# OSSC_HDMI_Audio.net
KiCad netlist of a schematic drawn in EAGLE
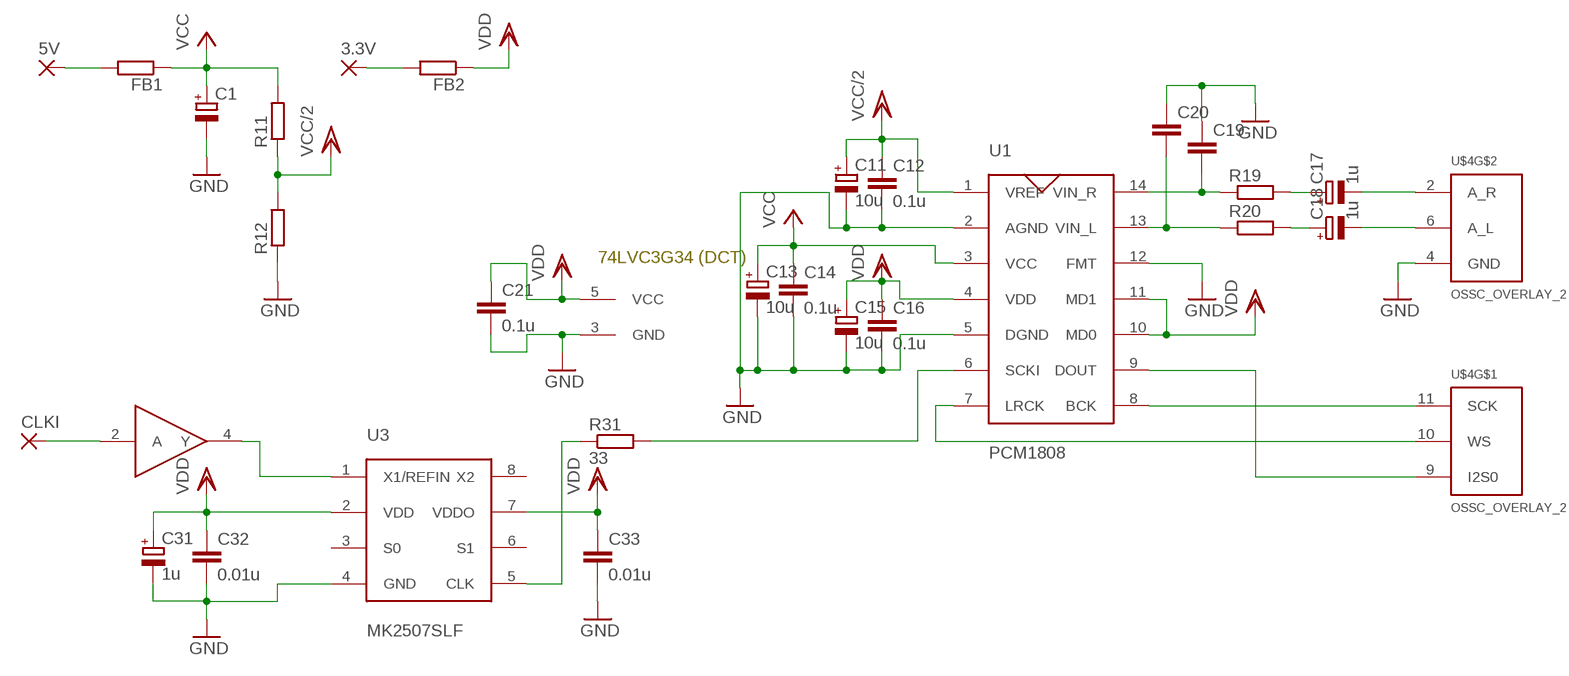
[diagram p0: schematic, sheet 1]

(export (version "E")
  (design (tool "Eeschema 10.0.6"))
  (components
    (comp (ref "3.3V")
      (value "SMD2")
      (footprint "eagle-import:SMD1,27-2,54")
      (libsource (lib "eagle-import") (part "SMD2"))
    )
    (comp (ref "5V")
      (value "SMD2")
      (footprint "eagle-import:SMD1,27-2,54")
      (libsource (lib "eagle-import") (part "SMD2"))
    )
    (comp (ref "C1")
      (value "CPOL-EUSMCC")
      (footprint "eagle-import:SMC_C")
      (libsource (lib "eagle-import") (part "CPOL-EUSMCC"))
    )
    (comp (ref "C11")
      (value "10u")
      (footprint "eagle-import:SMC_A")
      (libsource (lib "eagle-import") (part "CPOL-EUSMCA"))
    )
    (comp (ref "C12")
      (value "0.1u")
      (footprint "eagle-import:C0603")
      (libsource (lib "eagle-import") (part "C-EUC0603"))
    )
    (comp (ref "C13")
      (value "10u")
      (footprint "eagle-import:SMC_A")
      (libsource (lib "eagle-import") (part "CPOL-EUSMCA"))
    )
    (comp (ref "C14")
      (value "0.1u")
      (footprint "eagle-import:C0603")
      (libsource (lib "eagle-import") (part "C-EUC0603"))
    )
    (comp (ref "C15")
      (value "10u")
      (footprint "eagle-import:SMC_A")
      (libsource (lib "eagle-import") (part "CPOL-EUSMCA"))
    )
    (comp (ref "C16")
      (value "0.1u")
      (footprint "eagle-import:C0603")
      (libsource (lib "eagle-import") (part "C-EUC0603"))
    )
    (comp (ref "C17")
      (value "1u")
      (footprint "eagle-import:SMC_A")
      (libsource (lib "eagle-import") (part "CPOL-EUSMCA"))
    )
    (comp (ref "C18")
      (value "1u")
      (footprint "eagle-import:SMC_A")
      (libsource (lib "eagle-import") (part "CPOL-EUSMCA"))
    )
    (comp (ref "C19")
      (value "C-EUC0603")
      (footprint "eagle-import:C0603")
      (libsource (lib "eagle-import") (part "C-EUC0603"))
    )
    (comp (ref "C20")
      (value "C-EUC0603")
      (footprint "eagle-import:C0603")
      (libsource (lib "eagle-import") (part "C-EUC0603"))
    )
    (comp (ref "C21")
      (value "0.1u")
      (footprint "eagle-import:C0603")
      (libsource (lib "eagle-import") (part "C-EUC0603"))
    )
    (comp (ref "C31")
      (value "1u")
      (footprint "eagle-import:SMC_A")
      (libsource (lib "eagle-import") (part "CPOL-EUSMCA"))
    )
    (comp (ref "C32")
      (value "0.01u")
      (footprint "eagle-import:C0603")
      (libsource (lib "eagle-import") (part "C-EUC0603"))
    )
    (comp (ref "C33")
      (value "0.01u")
      (footprint "eagle-import:C0603")
      (libsource (lib "eagle-import") (part "C-EUC0603"))
    )
    (comp (ref "CLKI")
      (value "SMD2")
      (footprint "eagle-import:SMD1,27-2,54")
      (libsource (lib "eagle-import") (part "SMD2"))
    )
    (comp (ref "FB1")
      (value "R-EU_R0603")
      (footprint "eagle-import:R0603")
      (libsource (lib "eagle-import") (part "R-EU_R0603"))
    )
    (comp (ref "FB2")
      (value "R-EU_R0603")
      (footprint "eagle-import:R0603")
      (libsource (lib "eagle-import") (part "R-EU_R0603"))
    )
    (comp (ref "R11")
      (value "R-EU_R0603")
      (footprint "eagle-import:R0603")
      (libsource (lib "eagle-import") (part "R-EU_R0603"))
    )
    (comp (ref "R12")
      (value "R-EU_R0603")
      (footprint "eagle-import:R0603")
      (libsource (lib "eagle-import") (part "R-EU_R0603"))
    )
    (comp (ref "R19")
      (value "R-EU_R0603")
      (footprint "eagle-import:R0603")
      (libsource (lib "eagle-import") (part "R-EU_R0603"))
    )
    (comp (ref "R20")
      (value "R-EU_R0603")
      (footprint "eagle-import:R0603")
      (libsource (lib "eagle-import") (part "R-EU_R0603"))
    )
    (comp (ref "R31")
      (value "33")
      (footprint "eagle-import:R0603")
      (libsource (lib "eagle-import") (part "R-EU_R0603"))
    )
    (comp (ref "U$4")
      (value "OSSC_OVERLAY_2")
      (footprint "eagle-import:OSSC_OVERLAY_2")
      (libsource (lib "eagle-import") (part "OSSC_OVERLAY_2"))
    )
    (comp (ref "U1")
      (value "PCM1808")
      (footprint "eagle-import:PCM1808")
      (libsource (lib "eagle-import") (part "PCM1808"))
    )
    (comp (ref "U2")
      (value "74LVC1G34")
      (footprint "eagle-import:74LVC1G34DCK")
      (libsource (lib "eagle-import") (part "74LVC1G34"))
    )
    (comp (ref "U3")
      (value "MK2507SLF")
      (footprint "eagle-import:SOIC8")
      (libsource (lib "eagle-import") (part "MK2507SLF"))
    )
  )
  (nets
    (net (code "1") (name "GND") (class "Default")
      (node (ref "C1") (pin "-") (pinfunction "-_-") (pintype "passive"))
      (node (ref "C11") (pin "-") (pinfunction "-_-") (pintype "passive"))
      (node (ref "C12") (pin "2") (pinfunction "2_2") (pintype "passive"))
      (node (ref "C13") (pin "-") (pinfunction "-_-") (pintype "passive"))
      (node (ref "C14") (pin "2") (pinfunction "2_2") (pintype "passive"))
      (node (ref "C15") (pin "-") (pinfunction "-_-") (pintype "passive"))
      (node (ref "C16") (pin "2") (pinfunction "2_2") (pintype "passive"))
      (node (ref "C19") (pin "1") (pinfunction "1_1") (pintype "passive"))
      (node (ref "C20") (pin "1") (pinfunction "1_1") (pintype "passive"))
      (node (ref "C21") (pin "2") (pinfunction "2_2") (pintype "passive"))
      (node (ref "C31") (pin "-") (pinfunction "-_-") (pintype "passive"))
      (node (ref "C32") (pin "2") (pinfunction "2_2") (pintype "passive"))
      (node (ref "C33") (pin "2") (pinfunction "2_2") (pintype "passive"))
      (node (ref "R12") (pin "1") (pinfunction "1_1") (pintype "passive"))
      (node (ref "U$4") (pin "4") (pinfunction "GND_4") (pintype "bidirectional"))
      (node (ref "U1") (pin "12") (pinfunction "FMT_12") (pintype "bidirectional"))
      (node (ref "U1") (pin "2") (pinfunction "AGND_2") (pintype "bidirectional"))
      (node (ref "U1") (pin "5") (pinfunction "DGND_5") (pintype "bidirectional"))
      (node (ref "U2") (pin "3") (pinfunction "GND_3") (pintype "bidirectional"))
      (node (ref "U3") (pin "4") (pinfunction "GND_4") (pintype "bidirectional"))
    )
    (net (code "2") (name "Net-(3.3V-P)") (class "Default")
      (node (ref "3.3V") (pin "1") (pinfunction "P_1") (pintype "passive"))
      (node (ref "FB2") (pin "2") (pinfunction "2_2") (pintype "passive"))
    )
    (net (code "3") (name "Net-(5V-P)") (class "Default")
      (node (ref "5V") (pin "1") (pinfunction "P_1") (pintype "passive"))
      (node (ref "FB1") (pin "2") (pinfunction "2_2") (pintype "passive"))
    )
    (net (code "4") (name "Net-(C17-Pad+)") (class "Default")
      (node (ref "C17") (pin "+") (pinfunction "+_+") (pintype "passive"))
      (node (ref "R19") (pin "2") (pinfunction "2_2") (pintype "passive"))
    )
    (net (code "5") (name "Net-(C18-Pad+)") (class "Default")
      (node (ref "C18") (pin "+") (pinfunction "+_+") (pintype "passive"))
      (node (ref "R20") (pin "2") (pinfunction "2_2") (pintype "passive"))
    )
    (net (code "6") (name "Net-(CLKI-P)") (class "Default")
      (node (ref "CLKI") (pin "1") (pinfunction "P_1") (pintype "passive"))
      (node (ref "U2") (pin "2") (pinfunction "A_2") (pintype "bidirectional"))
    )
    (net (code "7") (name "Net-(U$4A-I2S0)") (class "Default")
      (node (ref "U$4") (pin "9") (pinfunction "I2S0_9") (pintype "bidirectional"))
      (node (ref "U1") (pin "9") (pinfunction "DOUT_9") (pintype "bidirectional"))
    )
    (net (code "8") (name "Net-(U$4A-SCK)") (class "Default")
      (node (ref "U$4") (pin "11") (pinfunction "SCK_11") (pintype "bidirectional"))
      (node (ref "U1") (pin "8") (pinfunction "BCK_8") (pintype "bidirectional"))
    )
    (net (code "9") (name "Net-(U$4A-WS)") (class "Default")
      (node (ref "U$4") (pin "10") (pinfunction "WS_10") (pintype "bidirectional"))
      (node (ref "U1") (pin "7") (pinfunction "LRCK_7") (pintype "bidirectional"))
    )
    (net (code "10") (name "Net-(U$4B-A_L)") (class "Default")
      (node (ref "C18") (pin "-") (pinfunction "-_-") (pintype "passive"))
      (node (ref "U$4") (pin "6") (pinfunction "A_L_6") (pintype "bidirectional"))
    )
    (net (code "11") (name "Net-(U$4B-A_R)") (class "Default")
      (node (ref "C17") (pin "-") (pinfunction "-_-") (pintype "passive"))
      (node (ref "U$4") (pin "2") (pinfunction "A_R_2") (pintype "bidirectional"))
    )
    (net (code "12") (name "Net-(U1-SCKI)") (class "Default")
      (node (ref "R31") (pin "2") (pinfunction "2_2") (pintype "passive"))
      (node (ref "U1") (pin "6") (pinfunction "SCKI_6") (pintype "bidirectional"))
    )
    (net (code "13") (name "Net-(U1-VIN_L)") (class "Default")
      (node (ref "C20") (pin "2") (pinfunction "2_2") (pintype "passive"))
      (node (ref "R20") (pin "1") (pinfunction "1_1") (pintype "passive"))
      (node (ref "U1") (pin "13") (pinfunction "VIN_L_13") (pintype "bidirectional"))
    )
    (net (code "14") (name "Net-(U1-VIN_R)") (class "Default")
      (node (ref "C19") (pin "2") (pinfunction "2_2") (pintype "passive"))
      (node (ref "R19") (pin "1") (pinfunction "1_1") (pintype "passive"))
      (node (ref "U1") (pin "14") (pinfunction "VIN_R_14") (pintype "bidirectional"))
    )
    (net (code "15") (name "Net-(U2A-Y)") (class "Default")
      (node (ref "U2") (pin "4") (pinfunction "Y_4") (pintype "bidirectional"))
      (node (ref "U3") (pin "1") (pinfunction "X1/REFIN_1") (pintype "bidirectional"))
    )
    (net (code "16") (name "Net-(U3-CLK)") (class "Default")
      (node (ref "R31") (pin "1") (pinfunction "1_1") (pintype "passive"))
      (node (ref "U3") (pin "5") (pinfunction "CLK_5") (pintype "bidirectional"))
    )
    (net (code "17") (name "VCC") (class "Default")
      (node (ref "C1") (pin "+") (pinfunction "+_+") (pintype "passive"))
      (node (ref "C13") (pin "+") (pinfunction "+_+") (pintype "passive"))
      (node (ref "C14") (pin "1") (pinfunction "1_1") (pintype "passive"))
      (node (ref "FB1") (pin "1") (pinfunction "1_1") (pintype "passive"))
      (node (ref "R11") (pin "2") (pinfunction "2_2") (pintype "passive"))
      (node (ref "U1") (pin "3") (pinfunction "VCC_3") (pintype "bidirectional"))
    )
    (net (code "18") (name "VCC{slash}2") (class "Default")
      (node (ref "C11") (pin "+") (pinfunction "+_+") (pintype "passive"))
      (node (ref "C12") (pin "1") (pinfunction "1_1") (pintype "passive"))
      (node (ref "R11") (pin "1") (pinfunction "1_1") (pintype "passive"))
      (node (ref "R12") (pin "2") (pinfunction "2_2") (pintype "passive"))
      (node (ref "U1") (pin "1") (pinfunction "VREF_1") (pintype "bidirectional"))
    )
    (net (code "19") (name "VDD") (class "Default")
      (node (ref "C15") (pin "+") (pinfunction "+_+") (pintype "passive"))
      (node (ref "C16") (pin "1") (pinfunction "1_1") (pintype "passive"))
      (node (ref "C21") (pin "1") (pinfunction "1_1") (pintype "passive"))
      (node (ref "C31") (pin "+") (pinfunction "+_+") (pintype "passive"))
      (node (ref "C32") (pin "1") (pinfunction "1_1") (pintype "passive"))
      (node (ref "C33") (pin "1") (pinfunction "1_1") (pintype "passive"))
      (node (ref "FB2") (pin "1") (pinfunction "1_1") (pintype "passive"))
      (node (ref "U1") (pin "10") (pinfunction "MD0_10") (pintype "bidirectional"))
      (node (ref "U1") (pin "11") (pinfunction "MD1_11") (pintype "bidirectional"))
      (node (ref "U1") (pin "4") (pinfunction "VDD_4") (pintype "bidirectional"))
      (node (ref "U2") (pin "5") (pinfunction "VCC_5") (pintype "bidirectional"))
      (node (ref "U3") (pin "2") (pinfunction "VDD_2") (pintype "bidirectional"))
      (node (ref "U3") (pin "7") (pinfunction "VDDO_7") (pintype "bidirectional"))
    )
    (net (code "20") (name "unconnected-(U3-S0-Pad3)") (class "Default")
      (node (ref "U3") (pin "3") (pinfunction "S0_3") (pintype "bidirectional"))
    )
    (net (code "21") (name "unconnected-(U3-S1-Pad6)") (class "Default")
      (node (ref "U3") (pin "6") (pinfunction "S1_6") (pintype "bidirectional"))
    )
    (net (code "22") (name "unconnected-(U3-X2-Pad8)") (class "Default")
      (node (ref "U3") (pin "8") (pinfunction "X2_8") (pintype "bidirectional"))
    )
  )
)
